# Zio_Qwiic_Loudness_Sensor.net
KiCad netlist of a schematic drawn in EAGLE
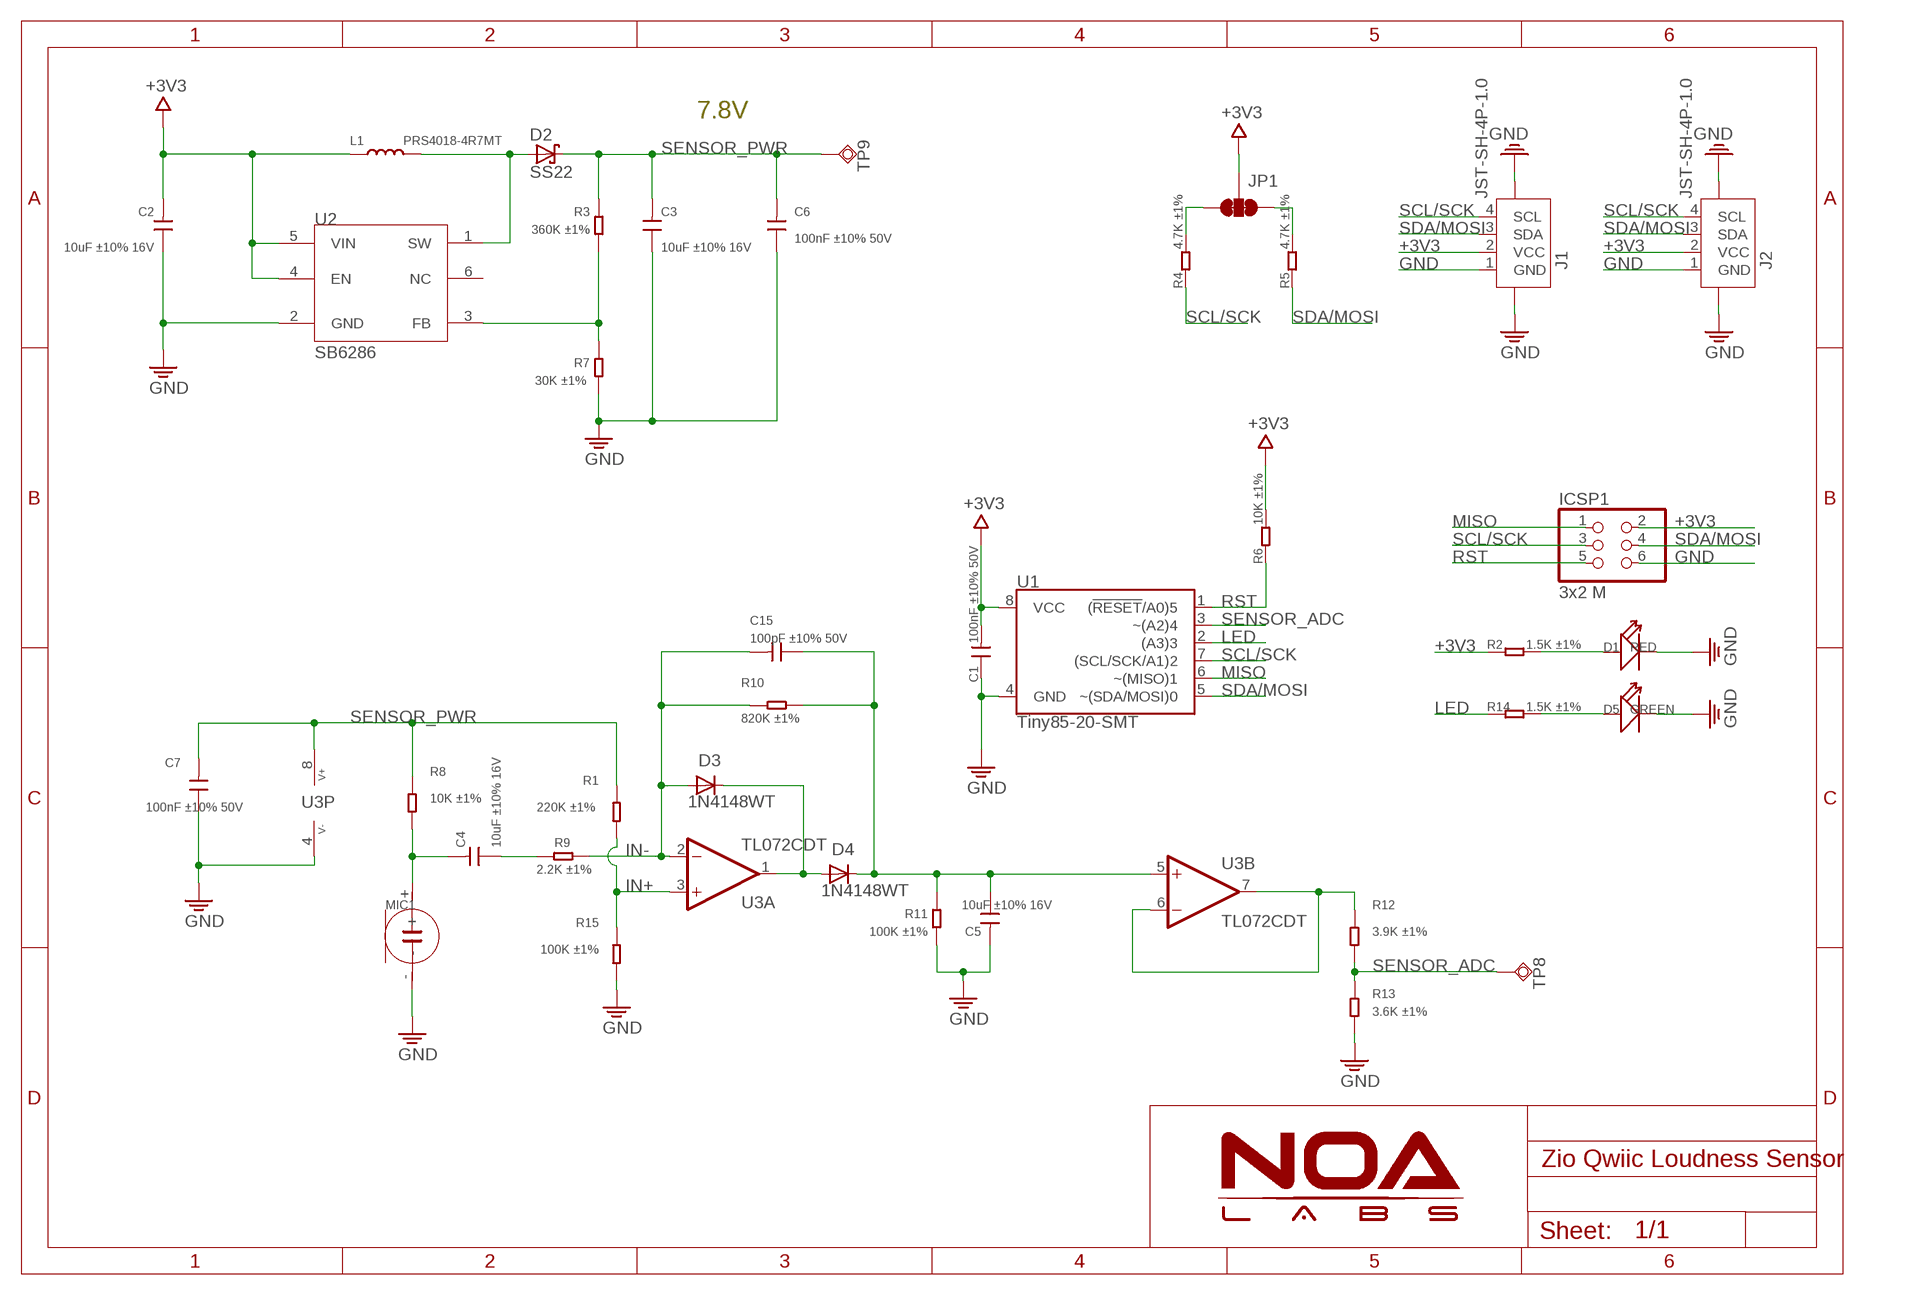
[diagram p0: schematic, sheet 1]

(export (version "E")
  (design (tool "Eeschema 10.0.6"))
  (components
    (comp (ref "C1")
      (value "100nF ±10% 50V")
      (footprint "eagle-import:C0603")
      (libsource (lib "eagle-import") (part "RCL_1838970_C-0603"))
    )
    (comp (ref "C2")
      (value "10uF ±10% 16V")
      (footprint "eagle-import:C0603")
      (libsource (lib "eagle-import") (part "RCL_1838970_C-0603"))
    )
    (comp (ref "C3")
      (value "10uF ±10% 16V")
      (footprint "eagle-import:0603")
      (libsource (lib "eagle-import") (part "C-0603"))
    )
    (comp (ref "C4")
      (value "10uF ±10% 16V")
      (footprint "eagle-import:0603")
      (libsource (lib "eagle-import") (part "C-0603"))
    )
    (comp (ref "C5")
      (value "10uF ±10% 16V")
      (footprint "eagle-import:0603")
      (libsource (lib "eagle-import") (part "C-0603"))
    )
    (comp (ref "C6")
      (value "100nF ±10% 50V")
      (footprint "eagle-import:C0603")
      (libsource (lib "eagle-import") (part "RCL_1838970_C-0603"))
    )
    (comp (ref "C7")
      (value "100nF ±10% 50V")
      (footprint "eagle-import:C0603")
      (libsource (lib "eagle-import") (part "RCL_1838970_C-0603"))
    )
    (comp (ref "C15")
      (value "100pF ±10% 50V")
      (footprint "eagle-import:C0603")
      (libsource (lib "eagle-import") (part "RCL_1838970_C-0603"))
    )
    (comp (ref "D1")
      (value "RED")
      (footprint "eagle-import:LED-0603")
      (libsource (lib "eagle-import") (part "LED'0603'"))
    )
    (comp (ref "D2")
      (value "SS22")
      (footprint "eagle-import:SMA")
      (libsource (lib "eagle-import") (part "SCHOTTKY"))
    )
    (comp (ref "D3")
      (value "1N4148WT")
      (footprint "eagle-import:SOD523")
      (libsource (lib "eagle-import") (part "BA277"))
    )
    (comp (ref "D4")
      (value "1N4148WT")
      (footprint "eagle-import:SOD523")
      (libsource (lib "eagle-import") (part "BA277"))
    )
    (comp (ref "D5")
      (value "GREEN")
      (footprint "eagle-import:LED-0603")
      (libsource (lib "eagle-import") (part "LED'0603'"))
    )
    (comp (ref "ICSP1")
      (value "3x2 M")
      (footprint "eagle-import:2X03")
      (libsource (lib "eagle-import") (part "PINHD-2X3"))
    )
    (comp (ref "J1")
      (value "JST-SH-4P-1.0")
      (footprint "eagle-import:JST-SH-4P")
      (libsource (lib "eagle-import") (part "JST-SH-4P-1.0"))
    )
    (comp (ref "J2")
      (value "JST-SH-4P-1.0")
      (footprint "eagle-import:JST-SH-4P")
      (libsource (lib "eagle-import") (part "JST-SH-4P-1.0"))
    )
    (comp (ref "JP1")
      (value "SMT-JUMPER_3_2-NC_TRACE")
      (footprint "eagle-import:SMT-JUMPER_3_2-NC_TRACE")
      (libsource (lib "eagle-import") (part "SMT-JUMPER_3_2-NC_TRACE"))
    )
    (comp (ref "L1")
      (value "PRS4018-4R7MT")
      (footprint "eagle-import:L4030")
      (libsource (lib "eagle-import") (part "L-4030"))
    )
    (comp (ref "MIC1")
      (value "MIC-2P(EAO-9745-PFA-C1033-28-008)")
      (footprint "eagle-import:MIC2-D9.7XH4.5MM")
      (fields (field (name "MPN") "EAO-9745-PFA-C1033-28-008"))
      (libsource (lib "eagle-import") (part "MIC-2P(EAO-9745-PFA-C1033-28-008)"))
    )
    (comp (ref "R1")
      (value "220K ±1%")
      (footprint "eagle-import:R0603")
      (libsource (lib "eagle-import") (part "R-0603"))
    )
    (comp (ref "R2")
      (value "1.5K ±1%")
      (footprint "eagle-import:R0603")
      (libsource (lib "eagle-import") (part "R-0603"))
    )
    (comp (ref "R3")
      (value "360K ±1%")
      (footprint "eagle-import:R0603")
      (libsource (lib "eagle-import") (part "R-0603"))
    )
    (comp (ref "R4")
      (value "4.7K ±1%")
      (footprint "eagle-import:R0603")
      (libsource (lib "eagle-import") (part "R-0603"))
    )
    (comp (ref "R5")
      (value "4.7K ±1%")
      (footprint "eagle-import:R0603")
      (libsource (lib "eagle-import") (part "R-0603"))
    )
    (comp (ref "R6")
      (value "10K ±1%")
      (footprint "eagle-import:R0603")
      (libsource (lib "eagle-import") (part "R-0603"))
    )
    (comp (ref "R7")
      (value "30K ±1%")
      (footprint "eagle-import:R0603")
      (libsource (lib "eagle-import") (part "R-0603"))
    )
    (comp (ref "R8")
      (value "10K ±1%")
      (footprint "eagle-import:R0603")
      (libsource (lib "eagle-import") (part "R-0603"))
    )
    (comp (ref "R9")
      (value "2.2K ±1%")
      (footprint "eagle-import:R0603")
      (libsource (lib "eagle-import") (part "R-0603"))
    )
    (comp (ref "R10")
      (value "820K ±1%")
      (footprint "eagle-import:R0603")
      (libsource (lib "eagle-import") (part "R-0603"))
    )
    (comp (ref "R11")
      (value "100K ±1%")
      (footprint "eagle-import:R0603")
      (libsource (lib "eagle-import") (part "R-0603"))
    )
    (comp (ref "R12")
      (value "3.9K ±1%")
      (footprint "eagle-import:R0603")
      (libsource (lib "eagle-import") (part "R-0603"))
    )
    (comp (ref "R13")
      (value "3.6K ±1%")
      (footprint "eagle-import:R0603")
      (libsource (lib "eagle-import") (part "R-0603"))
    )
    (comp (ref "R14")
      (value "1.5K ±1%")
      (footprint "eagle-import:R0603")
      (libsource (lib "eagle-import") (part "R-0603"))
    )
    (comp (ref "R15")
      (value "100K ±1%")
      (footprint "eagle-import:R0603")
      (libsource (lib "eagle-import") (part "R-0603"))
    )
    (comp (ref "TP8")
      (value "TPSQTP08R")
      (footprint "eagle-import:TP08R")
      (libsource (lib "eagle-import") (part "TPSQTP08R"))
    )
    (comp (ref "TP9")
      (value "TPSQTP12R")
      (footprint "eagle-import:TP12R")
      (libsource (lib "eagle-import") (part "TPSQTP12R"))
    )
    (comp (ref "U1")
      (value "Tiny85-20-SMT")
      (footprint "eagle-import:SO08-EIAJ_MCU")
      (libsource (lib "eagle-import") (part "ATTINY85-ARDUINOTINY85-20-SMT"))
    )
    (comp (ref "U2")
      (value "SB6286")
      (footprint "eagle-import:SOT23-6")
      (libsource (lib "eagle-import") (part "SDB628"))
    )
    (comp (ref "U3")
      (value "TL072CDT")
      (footprint "eagle-import:SO08")
      (libsource (lib "eagle-import") (part "TL072D"))
    )
  )
  (nets
    (net (code "1") (name "+3V3") (class "Default")
      (node (ref "C1") (pin "2") (pinfunction "2_2") (pintype "passive"))
      (node (ref "C2") (pin "2") (pinfunction "2_2") (pintype "passive"))
      (node (ref "ICSP1") (pin "2") (pinfunction "2_2") (pintype "passive"))
      (node (ref "J1") (pin "2") (pinfunction "VCC_2") (pintype "bidirectional"))
      (node (ref "J2") (pin "2") (pinfunction "VCC_2") (pintype "bidirectional"))
      (node (ref "JP1") (pin "2") (pinfunction "2_2") (pintype "passive"))
      (node (ref "L1") (pin "1") (pinfunction "1_1") (pintype "passive"))
      (node (ref "R2") (pin "1") (pinfunction "1_1") (pintype "passive"))
      (node (ref "R6") (pin "2") (pinfunction "2_2") (pintype "passive"))
      (node (ref "U1") (pin "8") (pinfunction "VCC_8") (pintype "bidirectional"))
      (node (ref "U2") (pin "4") (pinfunction "EN_4") (pintype "bidirectional"))
      (node (ref "U2") (pin "5") (pinfunction "VIN_5") (pintype "bidirectional"))
    )
    (net (code "2") (name "/IN+") (class "Default")
      (node (ref "R1") (pin "1") (pinfunction "1_1") (pintype "passive"))
      (node (ref "R15") (pin "2") (pinfunction "2_2") (pintype "passive"))
      (node (ref "U3") (pin "3") (pinfunction "+IN_3") (pintype "input"))
    )
    (net (code "3") (name "/IN-") (class "Default")
      (node (ref "C15") (pin "2") (pinfunction "2_2") (pintype "passive"))
      (node (ref "D3") (pin "2") (pinfunction "A_2") (pintype "passive"))
      (node (ref "R10") (pin "1") (pinfunction "1_1") (pintype "passive"))
      (node (ref "R9") (pin "1") (pinfunction "1_1") (pintype "passive"))
      (node (ref "U3") (pin "2") (pinfunction "-IN_2") (pintype "input"))
    )
    (net (code "4") (name "/LED") (class "Default")
      (node (ref "R14") (pin "1") (pinfunction "1_1") (pintype "passive"))
      (node (ref "U1") (pin "2") (pinfunction "(A3)3_2") (pintype "bidirectional"))
    )
    (net (code "5") (name "/MISO") (class "Default")
      (node (ref "ICSP1") (pin "1") (pinfunction "1_1") (pintype "passive"))
      (node (ref "U1") (pin "6") (pinfunction "~{(MISO})1_6") (pintype "bidirectional"))
    )
    (net (code "6") (name "/RST") (class "Default")
      (node (ref "ICSP1") (pin "5") (pinfunction "5_5") (pintype "passive"))
      (node (ref "R6") (pin "1") (pinfunction "1_1") (pintype "passive"))
      (node (ref "U1") (pin "1") (pinfunction "(~{RESET}/A0)5_1") (pintype "bidirectional"))
    )
    (net (code "7") (name "/SCL{slash}SCK") (class "Default")
      (node (ref "ICSP1") (pin "3") (pinfunction "3_3") (pintype "passive"))
      (node (ref "J1") (pin "4") (pinfunction "SCL_4") (pintype "bidirectional"))
      (node (ref "J2") (pin "4") (pinfunction "SCL_4") (pintype "bidirectional"))
      (node (ref "R4") (pin "1") (pinfunction "1_1") (pintype "passive"))
      (node (ref "U1") (pin "7") (pinfunction "(SCL/SCK/A1)2_7") (pintype "bidirectional"))
    )
    (net (code "8") (name "/SDA{slash}MOSI") (class "Default")
      (node (ref "ICSP1") (pin "4") (pinfunction "4_4") (pintype "passive"))
      (node (ref "J1") (pin "3") (pinfunction "SDA_3") (pintype "bidirectional"))
      (node (ref "J2") (pin "3") (pinfunction "SDA_3") (pintype "bidirectional"))
      (node (ref "R5") (pin "1") (pinfunction "1_1") (pintype "passive"))
      (node (ref "U1") (pin "5") (pinfunction "~{(SDA/MOSI})0_5") (pintype "bidirectional"))
    )
    (net (code "9") (name "/SENSOR_ADC") (class "Default")
      (node (ref "R12") (pin "1") (pinfunction "1_1") (pintype "passive"))
      (node (ref "R13") (pin "2") (pinfunction "2_2") (pintype "passive"))
      (node (ref "TP8") (pin "TP") (pinfunction "TP_TP") (pintype "input"))
      (node (ref "U1") (pin "3") (pinfunction "~{(A2})4_3") (pintype "bidirectional"))
    )
    (net (code "10") (name "/SENSOR_PWR") (class "Default")
      (node (ref "C3") (pin "2") (pinfunction "2_2") (pintype "passive"))
      (node (ref "C6") (pin "2") (pinfunction "2_2") (pintype "passive"))
      (node (ref "C7") (pin "2") (pinfunction "2_2") (pintype "passive"))
      (node (ref "D2") (pin "P$1") (pinfunction "C_P$1") (pintype "passive"))
      (node (ref "R1") (pin "2") (pinfunction "2_2") (pintype "passive"))
      (node (ref "R3") (pin "2") (pinfunction "2_2") (pintype "passive"))
      (node (ref "R8") (pin "2") (pinfunction "2_2") (pintype "passive"))
      (node (ref "TP9") (pin "TP") (pinfunction "TP_TP") (pintype "input"))
      (node (ref "U3") (pin "8") (pinfunction "V+_8") (pintype "power_in"))
    )
    (net (code "11") (name "GND") (class "Default")
      (node (ref "C1") (pin "1") (pinfunction "1_1") (pintype "passive"))
      (node (ref "C2") (pin "1") (pinfunction "1_1") (pintype "passive"))
      (node (ref "C3") (pin "1") (pinfunction "1_1") (pintype "passive"))
      (node (ref "C5") (pin "2") (pinfunction "2_2") (pintype "passive"))
      (node (ref "C6") (pin "1") (pinfunction "1_1") (pintype "passive"))
      (node (ref "C7") (pin "1") (pinfunction "1_1") (pintype "passive"))
      (node (ref "D1") (pin "-") (pinfunction "-_-") (pintype "passive"))
      (node (ref "D5") (pin "-") (pinfunction "-_-") (pintype "passive"))
      (node (ref "ICSP1") (pin "6") (pinfunction "6_6") (pintype "passive"))
      (node (ref "J1") (pin "1") (pinfunction "GND_1") (pintype "bidirectional"))
      (node (ref "J1") (pin "NC1") (pinfunction "5_NC1") (pintype "bidirectional"))
      (node (ref "J1") (pin "NC2") (pinfunction "6_NC2") (pintype "bidirectional"))
      (node (ref "J2") (pin "1") (pinfunction "GND_1") (pintype "bidirectional"))
      (node (ref "J2") (pin "NC1") (pinfunction "5_NC1") (pintype "bidirectional"))
      (node (ref "J2") (pin "NC2") (pinfunction "6_NC2") (pintype "bidirectional"))
      (node (ref "MIC1") (pin "-") (pinfunction "-_-") (pintype "bidirectional"))
      (node (ref "R11") (pin "1") (pinfunction "1_1") (pintype "passive"))
      (node (ref "R13") (pin "1") (pinfunction "1_1") (pintype "passive"))
      (node (ref "R15") (pin "1") (pinfunction "1_1") (pintype "passive"))
      (node (ref "R7") (pin "1") (pinfunction "1_1") (pintype "passive"))
      (node (ref "U1") (pin "4") (pinfunction "GND_4") (pintype "bidirectional"))
      (node (ref "U2") (pin "2") (pinfunction "GND_2") (pintype "bidirectional"))
      (node (ref "U3") (pin "4") (pinfunction "V-_4") (pintype "power_in"))
    )
    (net (code "12") (name "Net-(C4-Pad1)") (class "Default")
      (node (ref "C4") (pin "1") (pinfunction "1_1") (pintype "passive"))
      (node (ref "R9") (pin "2") (pinfunction "2_2") (pintype "passive"))
    )
    (net (code "13") (name "Net-(C4-Pad2)") (class "Default")
      (node (ref "C4") (pin "2") (pinfunction "2_2") (pintype "passive"))
      (node (ref "MIC1") (pin "+") (pinfunction "+_+") (pintype "bidirectional"))
      (node (ref "R8") (pin "1") (pinfunction "1_1") (pintype "passive"))
    )
    (net (code "14") (name "Net-(D1-Pad+)") (class "Default")
      (node (ref "D1") (pin "+") (pinfunction "+_+") (pintype "passive"))
      (node (ref "R2") (pin "2") (pinfunction "2_2") (pintype "passive"))
    )
    (net (code "15") (name "Net-(D2-A)") (class "Default")
      (node (ref "D2") (pin "P$2") (pinfunction "A_P$2") (pintype "passive"))
      (node (ref "L1") (pin "2") (pinfunction "2_2") (pintype "passive"))
      (node (ref "U2") (pin "1") (pinfunction "SW_1") (pintype "bidirectional"))
    )
    (net (code "16") (name "Net-(D3-K)") (class "Default")
      (node (ref "D3") (pin "1") (pinfunction "K_1") (pintype "passive"))
      (node (ref "D4") (pin "2") (pinfunction "A_2") (pintype "passive"))
      (node (ref "U3") (pin "1") (pinfunction "OUT_1") (pintype "output"))
    )
    (net (code "17") (name "Net-(D4-K)") (class "Default")
      (node (ref "C15") (pin "1") (pinfunction "1_1") (pintype "passive"))
      (node (ref "C5") (pin "1") (pinfunction "1_1") (pintype "passive"))
      (node (ref "D4") (pin "1") (pinfunction "K_1") (pintype "passive"))
      (node (ref "R10") (pin "2") (pinfunction "2_2") (pintype "passive"))
      (node (ref "R11") (pin "2") (pinfunction "2_2") (pintype "passive"))
      (node (ref "U3") (pin "5") (pinfunction "+IN_5") (pintype "input"))
    )
    (net (code "18") (name "Net-(D5-Pad+)") (class "Default")
      (node (ref "D5") (pin "+") (pinfunction "+_+") (pintype "passive"))
      (node (ref "R14") (pin "2") (pinfunction "2_2") (pintype "passive"))
    )
    (net (code "19") (name "Net-(JP1-Pad1)") (class "Default")
      (node (ref "JP1") (pin "1") (pinfunction "1_1") (pintype "passive"))
      (node (ref "R5") (pin "2") (pinfunction "2_2") (pintype "passive"))
    )
    (net (code "20") (name "Net-(JP1-Pad3)") (class "Default")
      (node (ref "JP1") (pin "3") (pinfunction "3_3") (pintype "passive"))
      (node (ref "R4") (pin "2") (pinfunction "2_2") (pintype "passive"))
    )
    (net (code "21") (name "Net-(U2-FB)") (class "Default")
      (node (ref "R3") (pin "1") (pinfunction "1_1") (pintype "passive"))
      (node (ref "R7") (pin "2") (pinfunction "2_2") (pintype "passive"))
      (node (ref "U2") (pin "3") (pinfunction "FB_3") (pintype "bidirectional"))
    )
    (net (code "22") (name "Net-(U3B--IN)") (class "Default")
      (node (ref "R12") (pin "2") (pinfunction "2_2") (pintype "passive"))
      (node (ref "U3") (pin "6") (pinfunction "-IN_6") (pintype "input"))
      (node (ref "U3") (pin "7") (pinfunction "OUT_7") (pintype "output"))
    )
    (net (code "23") (name "unconnected-(U2-NC-Pad6)") (class "Default")
      (node (ref "U2") (pin "6") (pinfunction "NC_6") (pintype "bidirectional"))
    )
  )
)
